# PG4_SHEET2.net
KiCad netlist of a schematic drawn in Altium Designer
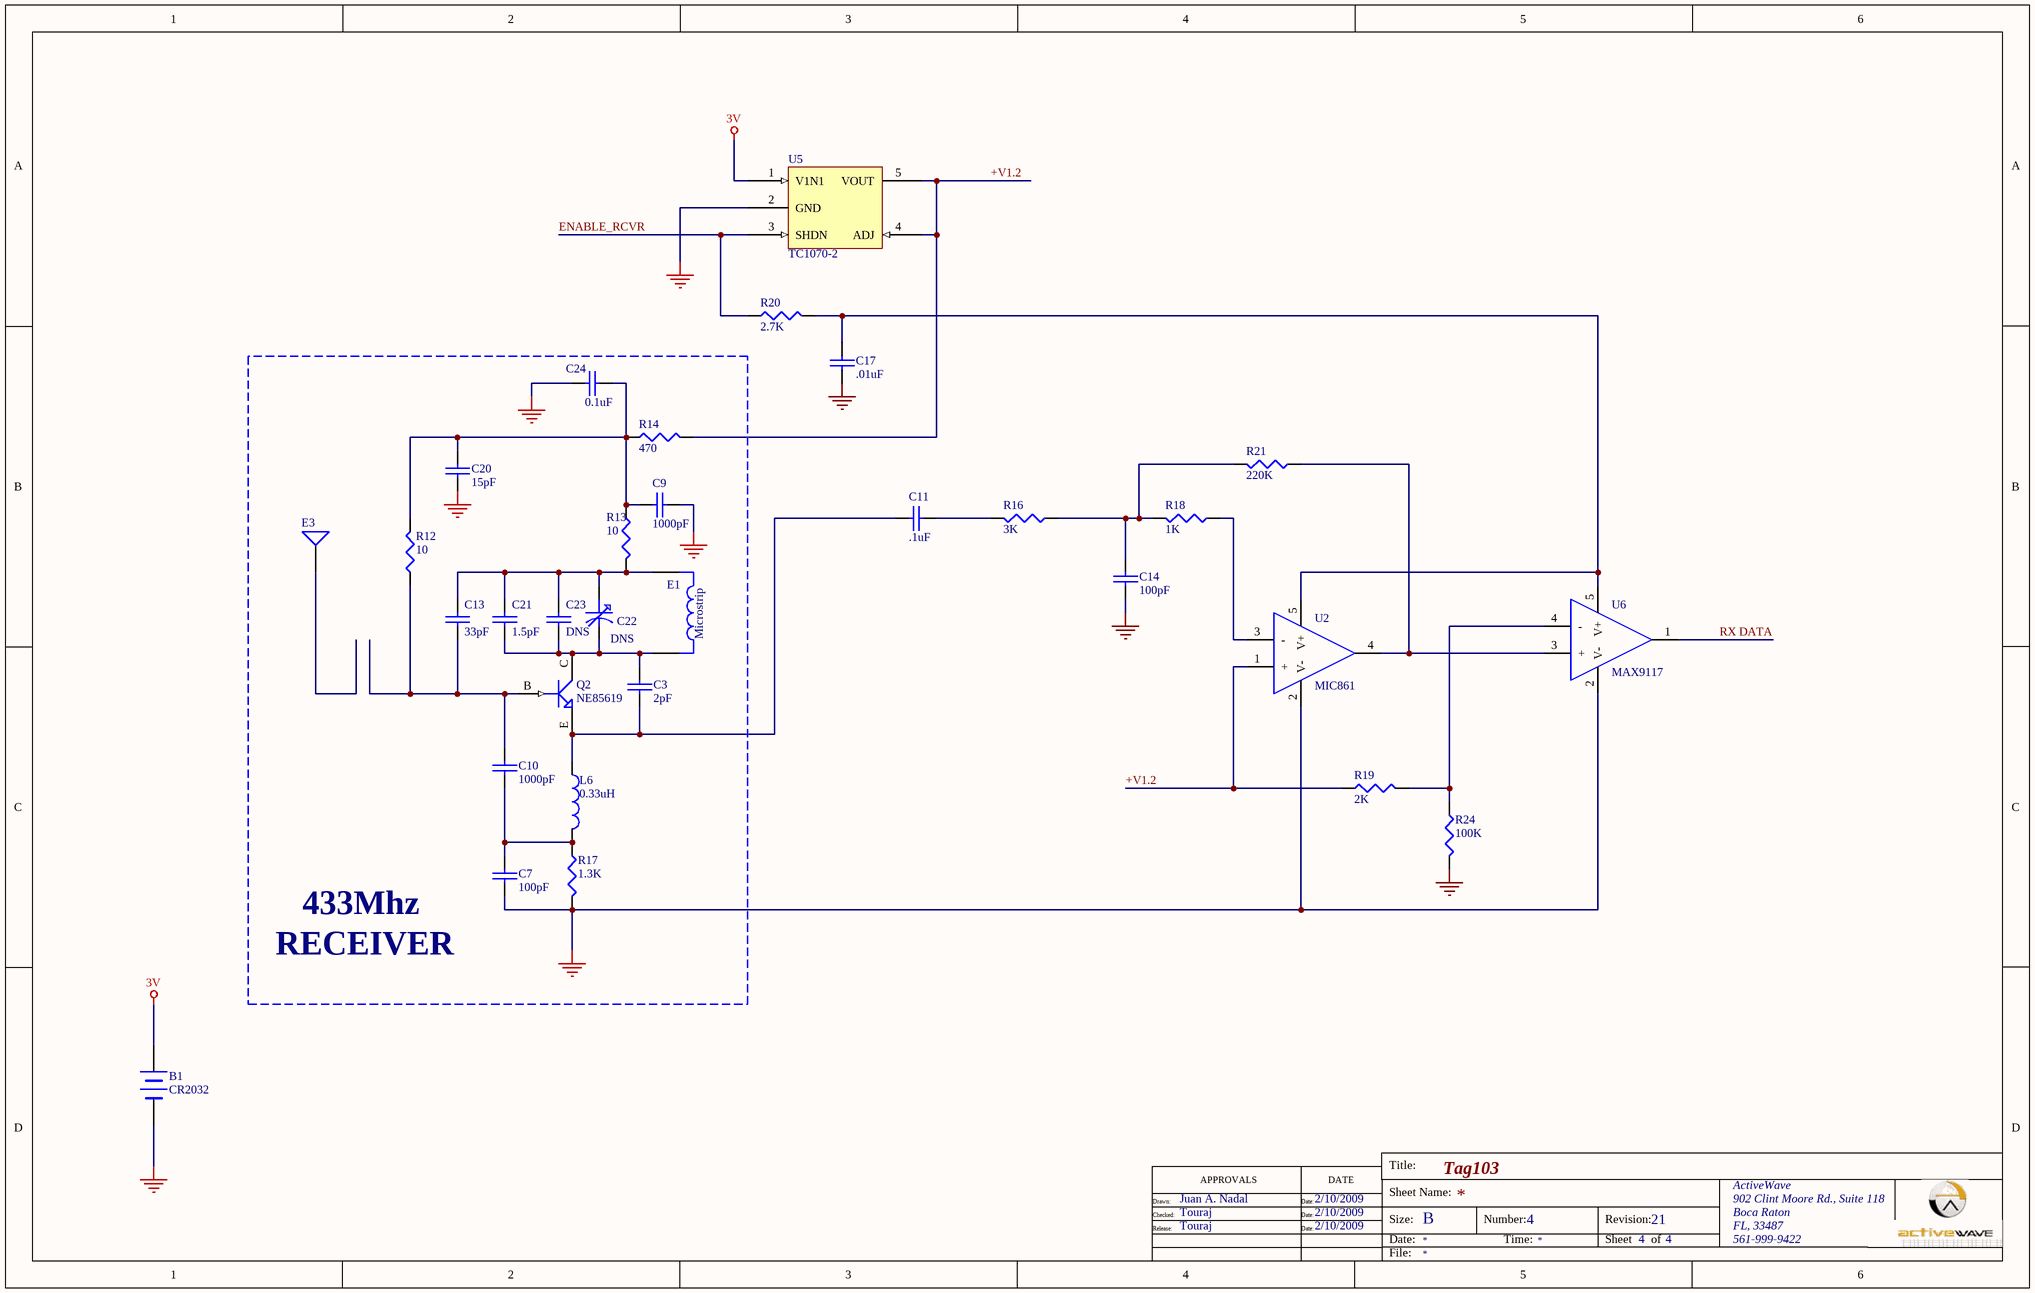
[diagram p0: PG4 SHEET2.schdoc]

(export (version "E")
  (design (tool "Eeschema 10.0.6"))
  (components
    (comp (ref "B1")
      (value "CR2032")
      (footprint "BATT HOLDER1")
      (description "Battery")
      (fields (field (name "Comment") "BATT HOLDER COIN CR2032 CUT"))
      (libsource (lib "ActiveWave MasterLib") (part "BATTERY2"))
    )
    (comp (ref "C3")
      (value "2pF")
      (footprint "0603")
      (description "Capacitor")
      (fields (field (name "Comment") "2 pF"))
      (libsource (lib "ActiveWave MasterLib") (part "CAP-0603"))
    )
    (comp (ref "C7")
      (value "100pF")
      (footprint "0603")
      (description "Capacitor")
      (fields (field (name "Comment") "100 pF"))
      (libsource (lib "ActiveWave MasterLib") (part "CAP-0603"))
    )
    (comp (ref "C9")
      (value "1000pF")
      (footprint "0603")
      (description "Capacitor")
      (fields (field (name "Comment") "1000 pF"))
      (libsource (lib "ActiveWave MasterLib") (part "CAP-0603"))
    )
    (comp (ref "C10")
      (value "1000pF")
      (footprint "0603")
      (description "Capacitor")
      (fields (field (name "Comment") "1000 pF"))
      (libsource (lib "ActiveWave MasterLib") (part "CAP-0603"))
    )
    (comp (ref "C11")
      (value ".1uF")
      (footprint "0603")
      (description "Capacitor")
      (libsource (lib "ActiveWave MasterLib") (part "CAP-0603"))
    )
    (comp (ref "C13")
      (value "33pF")
      (footprint "0603")
      (description "Capacitor")
      (fields (field (name "Comment") "33 pF"))
      (libsource (lib "ActiveWave MasterLib") (part "CAP-0603"))
    )
    (comp (ref "C14")
      (value "100pF")
      (footprint "0603")
      (description "Capacitor")
      (libsource (lib "ActiveWave MasterLib") (part "CAP-0603"))
    )
    (comp (ref "C17")
      (value ".01uF")
      (footprint "0603")
      (description "Capacitor")
      (libsource (lib "ActiveWave MasterLib") (part "CAP-0603"))
    )
    (comp (ref "C20")
      (value "15pF")
      (footprint "0603")
      (description "Capacitor")
      (libsource (lib "ActiveWave MasterLib") (part "CAP-0603"))
    )
    (comp (ref "C21")
      (value "1.5pF")
      (footprint "0603")
      (description "Capacitor")
      (libsource (lib "ActiveWave MasterLib") (part "CAP-0603"))
    )
    (comp (ref "C22") (value "DNS") (footprint "0603") (libsource (lib "*") (part "CAPACITOR VAR")))
    (comp (ref "C23")
      (value "DNS")
      (footprint "0603")
      (description "Capacitor")
      (libsource (lib "ActiveWave MasterLib") (part "CAP-0603"))
    )
    (comp (ref "C24")
      (value "0.1uF")
      (footprint "0603")
      (description "Capacitor")
      (fields (field (name "Comment") "0.1 uF"))
      (libsource (lib "ActiveWave MasterLib") (part "CAP-0603"))
    )
    (comp (ref "E1")
      (value "Microstrip")
      (footprint "Antenna")
      (fields (field (name "ITEM-DESCRIPTION") "Microstrip"))
      (libsource (lib "ActiveWave MasterLib") (part "ANTENNA"))
    )
    (comp (ref "E3")
      (value "*")
      (footprint "Antenna1")
      (libsource (lib "ActiveWave MasterLib") (part "Antenna1"))
    )
    (comp (ref "L6")
      (value "0.33uH")
      (footprint "0603")
      (libsource (lib "ActiveWave MasterLib") (part "INDUCTOR"))
    )
    (comp (ref "Q2")
      (value "NE85619")
      (footprint "3 PIN ULTRA SUPER MINI MOLD")
      (description "NPN Transistor")
      (libsource (lib "ActiveWave MasterLib") (part "NE85619"))
    )
    (comp (ref "R12")
      (value "10")
      (footprint "0603")
      (libsource (lib "ActiveWave MasterLib") (part "RES-0603"))
    )
    (comp (ref "R13")
      (value "10")
      (footprint "0603")
      (libsource (lib "ActiveWave MasterLib") (part "RES-0603"))
    )
    (comp (ref "R14")
      (value "470")
      (footprint "0603")
      (libsource (lib "ActiveWave MasterLib") (part "RES-0603"))
    )
    (comp (ref "R16")
      (value "3K")
      (footprint "0603")
      (fields (field (name "Comment") "22K"))
      (libsource (lib "ActiveWave MasterLib") (part "RES-0603"))
    )
    (comp (ref "R17")
      (value "1.3K")
      (footprint "0603")
      (fields (field (name "Comment") "2K"))
      (libsource (lib "ActiveWave MasterLib") (part "RES-0603"))
    )
    (comp (ref "R18")
      (value "1K")
      (footprint "0603")
      (libsource (lib "ActiveWave MasterLib") (part "RES-0603"))
    )
    (comp (ref "R19")
      (value "2K")
      (footprint "0603")
      (libsource (lib "ActiveWave MasterLib") (part "RES-0603"))
    )
    (comp (ref "R20")
      (value "2.7K")
      (footprint "0603")
      (libsource (lib "ActiveWave MasterLib") (part "RES-0603"))
    )
    (comp (ref "R21")
      (value "220K")
      (footprint "0603")
      (libsource (lib "ActiveWave MasterLib") (part "RES-0603"))
    )
    (comp (ref "R24")
      (value "100K")
      (footprint "0603")
      (libsource (lib "ActiveWave MasterLib") (part "RES-0603"))
    )
    (comp (ref "U2")
      (value "MIC861")
      (footprint "SC70")
      (libsource (lib "ActiveWave MasterLib") (part "OPAMP MIC861"))
    )
    (comp (ref "U5")
      (value "TC1070-2")
      (footprint "SOT23-5A")
      (fields (field (name "Comment") "TC1070"))
      (libsource (lib "ActiveWave MasterLib") (part "TC1070-2"))
    )
    (comp (ref "U6")
      (value "MAX9117")
      (footprint "SC70")
      (fields (field (name "Comment") "MAX9119EXK+"))
      (libsource (lib "ActiveWave MasterLib") (part "COMPARATOR MAX9117"))
    )
  )
  (nets
    (net (code "1") (name "/+V1.2") (class "Default")
      (node (ref "R14") (pin "2") (pinfunction "2_2") (pintype "passive"))
      (node (ref "R19") (pin "1") (pinfunction "1_1") (pintype "passive"))
      (node (ref "U2") (pin "1") (pinfunction "+_1") (pintype "passive"))
      (node (ref "U5") (pin "4") (pinfunction "ADJ_4") (pintype "input"))
      (node (ref "U5") (pin "5") (pinfunction "VOUT_5") (pintype "power_in"))
    )
    (net (code "2") (name "/ENABLE_RCVR") (class "Default")
      (node (ref "R20") (pin "1") (pinfunction "1_1") (pintype "passive"))
      (node (ref "U5") (pin "3") (pinfunction "SHDN_3") (pintype "input"))
    )
    (net (code "3") (name "/RX DATA") (class "Default")
      (node (ref "U6") (pin "1") (pinfunction "OUT_1") (pintype "passive"))
    )
    (net (code "4") (name "3V") (class "Default")
      (node (ref "B1") (pin "2") (pinfunction "+_2") (pintype "passive"))
      (node (ref "U5") (pin "1") (pinfunction "V1N1_1") (pintype "input"))
    )
    (net (code "5") (name "GND") (class "Default")
      (node (ref "B1") (pin "1") (pinfunction "-_1") (pintype "passive"))
      (node (ref "C14") (pin "1") (pinfunction "1_1") (pintype "passive"))
      (node (ref "C17") (pin "2") (pinfunction "2_2") (pintype "passive"))
      (node (ref "C20") (pin "2") (pinfunction "2_2") (pintype "passive"))
      (node (ref "C24") (pin "2") (pinfunction "2_2") (pintype "passive"))
      (node (ref "C7") (pin "2") (pinfunction "2_2") (pintype "passive"))
      (node (ref "C9") (pin "2") (pinfunction "2_2") (pintype "passive"))
      (node (ref "R17") (pin "2") (pinfunction "2_2") (pintype "passive"))
      (node (ref "R24") (pin "2") (pinfunction "2_2") (pintype "passive"))
      (node (ref "U2") (pin "2") (pinfunction "V-_2") (pintype "passive"))
      (node (ref "U5") (pin "2") (pinfunction "GND_2") (pintype "power_in"))
      (node (ref "U6") (pin "2") (pinfunction "V-_2") (pintype "passive"))
    )
    (net (code "6") (name "Net-(C10-Pad1)") (class "Default")
      (node (ref "C10") (pin "1") (pinfunction "1_1") (pintype "passive"))
      (node (ref "C13") (pin "2") (pinfunction "2_2") (pintype "passive"))
      (node (ref "Q2") (pin "B") (pinfunction "B_B") (pintype "input"))
      (node (ref "R12") (pin "1") (pinfunction "1_1") (pintype "passive"))
    )
    (net (code "7") (name "Net-(C10-Pad2)") (class "Default")
      (node (ref "C10") (pin "2") (pinfunction "2_2") (pintype "passive"))
      (node (ref "C7") (pin "1") (pinfunction "1_1") (pintype "passive"))
      (node (ref "L6") (pin "2") (pinfunction "2_2") (pintype "passive"))
      (node (ref "R17") (pin "1") (pinfunction "1_1") (pintype "passive"))
    )
    (net (code "8") (name "Net-(C11-Pad1)") (class "Default")
      (node (ref "C11") (pin "1") (pinfunction "1_1") (pintype "passive"))
      (node (ref "C3") (pin "2") (pinfunction "2_2") (pintype "passive"))
      (node (ref "L6") (pin "1") (pinfunction "1_1") (pintype "passive"))
      (node (ref "Q2") (pin "E") (pinfunction "E_E") (pintype "passive"))
    )
    (net (code "9") (name "Net-(C11-Pad2)") (class "Default")
      (node (ref "C11") (pin "2") (pinfunction "2_2") (pintype "passive"))
      (node (ref "R16") (pin "2") (pinfunction "2_2") (pintype "passive"))
    )
    (net (code "10") (name "Net-(C13-Pad1)") (class "Default")
      (node (ref "C13") (pin "1") (pinfunction "1_1") (pintype "passive"))
      (node (ref "C21") (pin "1") (pinfunction "1_1") (pintype "passive"))
      (node (ref "C22") (pin "1") (pinfunction "1_1") (pintype "passive"))
      (node (ref "C23") (pin "1") (pinfunction "1_1") (pintype "passive"))
      (node (ref "E1") (pin "1") (pinfunction "1_1") (pintype "passive"))
      (node (ref "R13") (pin "2") (pinfunction "2_2") (pintype "passive"))
    )
    (net (code "11") (name "Net-(C14-Pad2)") (class "Default")
      (node (ref "C14") (pin "2") (pinfunction "2_2") (pintype "passive"))
      (node (ref "R16") (pin "1") (pinfunction "1_1") (pintype "passive"))
      (node (ref "R18") (pin "2") (pinfunction "2_2") (pintype "passive"))
      (node (ref "R21") (pin "2") (pinfunction "2_2") (pintype "passive"))
    )
    (net (code "12") (name "Net-(C20-Pad1)") (class "Default")
      (node (ref "C20") (pin "1") (pinfunction "1_1") (pintype "passive"))
      (node (ref "C24") (pin "1") (pinfunction "1_1") (pintype "passive"))
      (node (ref "C9") (pin "1") (pinfunction "1_1") (pintype "passive"))
      (node (ref "R12") (pin "2") (pinfunction "2_2") (pintype "passive"))
      (node (ref "R13") (pin "1") (pinfunction "1_1") (pintype "passive"))
      (node (ref "R14") (pin "1") (pinfunction "1_1") (pintype "passive"))
    )
    (net (code "13") (name "Net-(C21-Pad2)") (class "Default")
      (node (ref "C21") (pin "2") (pinfunction "2_2") (pintype "passive"))
      (node (ref "C22") (pin "2") (pinfunction "2_2") (pintype "passive"))
      (node (ref "C23") (pin "2") (pinfunction "2_2") (pintype "passive"))
      (node (ref "C3") (pin "1") (pinfunction "1_1") (pintype "passive"))
      (node (ref "E1") (pin "2") (pinfunction "2_2") (pintype "passive"))
      (node (ref "Q2") (pin "C") (pinfunction "C_C") (pintype "passive"))
    )
    (net (code "14") (name "Net-(U2--)") (class "Default")
      (node (ref "R18") (pin "1") (pinfunction "1_1") (pintype "passive"))
      (node (ref "U2") (pin "3") (pinfunction "-_3") (pintype "passive"))
    )
    (net (code "15") (name "Net-(U2-OUT)") (class "Default")
      (node (ref "R21") (pin "1") (pinfunction "1_1") (pintype "passive"))
      (node (ref "U2") (pin "4") (pinfunction "OUT_4") (pintype "passive"))
      (node (ref "U6") (pin "3") (pinfunction "+_3") (pintype "passive"))
    )
    (net (code "16") (name "Net-(U2-V+)") (class "Default")
      (node (ref "C17") (pin "1") (pinfunction "1_1") (pintype "passive"))
      (node (ref "R20") (pin "2") (pinfunction "2_2") (pintype "passive"))
      (node (ref "U2") (pin "5") (pinfunction "V+_5") (pintype "passive"))
      (node (ref "U6") (pin "5") (pinfunction "V+_5") (pintype "passive"))
    )
    (net (code "17") (name "Net-(U6--)") (class "Default")
      (node (ref "R19") (pin "2") (pinfunction "2_2") (pintype "passive"))
      (node (ref "R24") (pin "1") (pinfunction "1_1") (pintype "passive"))
      (node (ref "U6") (pin "4") (pinfunction "-_4") (pintype "passive"))
    )
    (net (code "18") (name "unconnected-(E3-Pad1)") (class "Default")
      (node (ref "E3") (pin "1") (pinfunction "1_1") (pintype "passive"))
    )
  )
)
